# SoftCore_SA_P2_PG5.net
KiCad netlist of a schematic drawn in Altium Designer
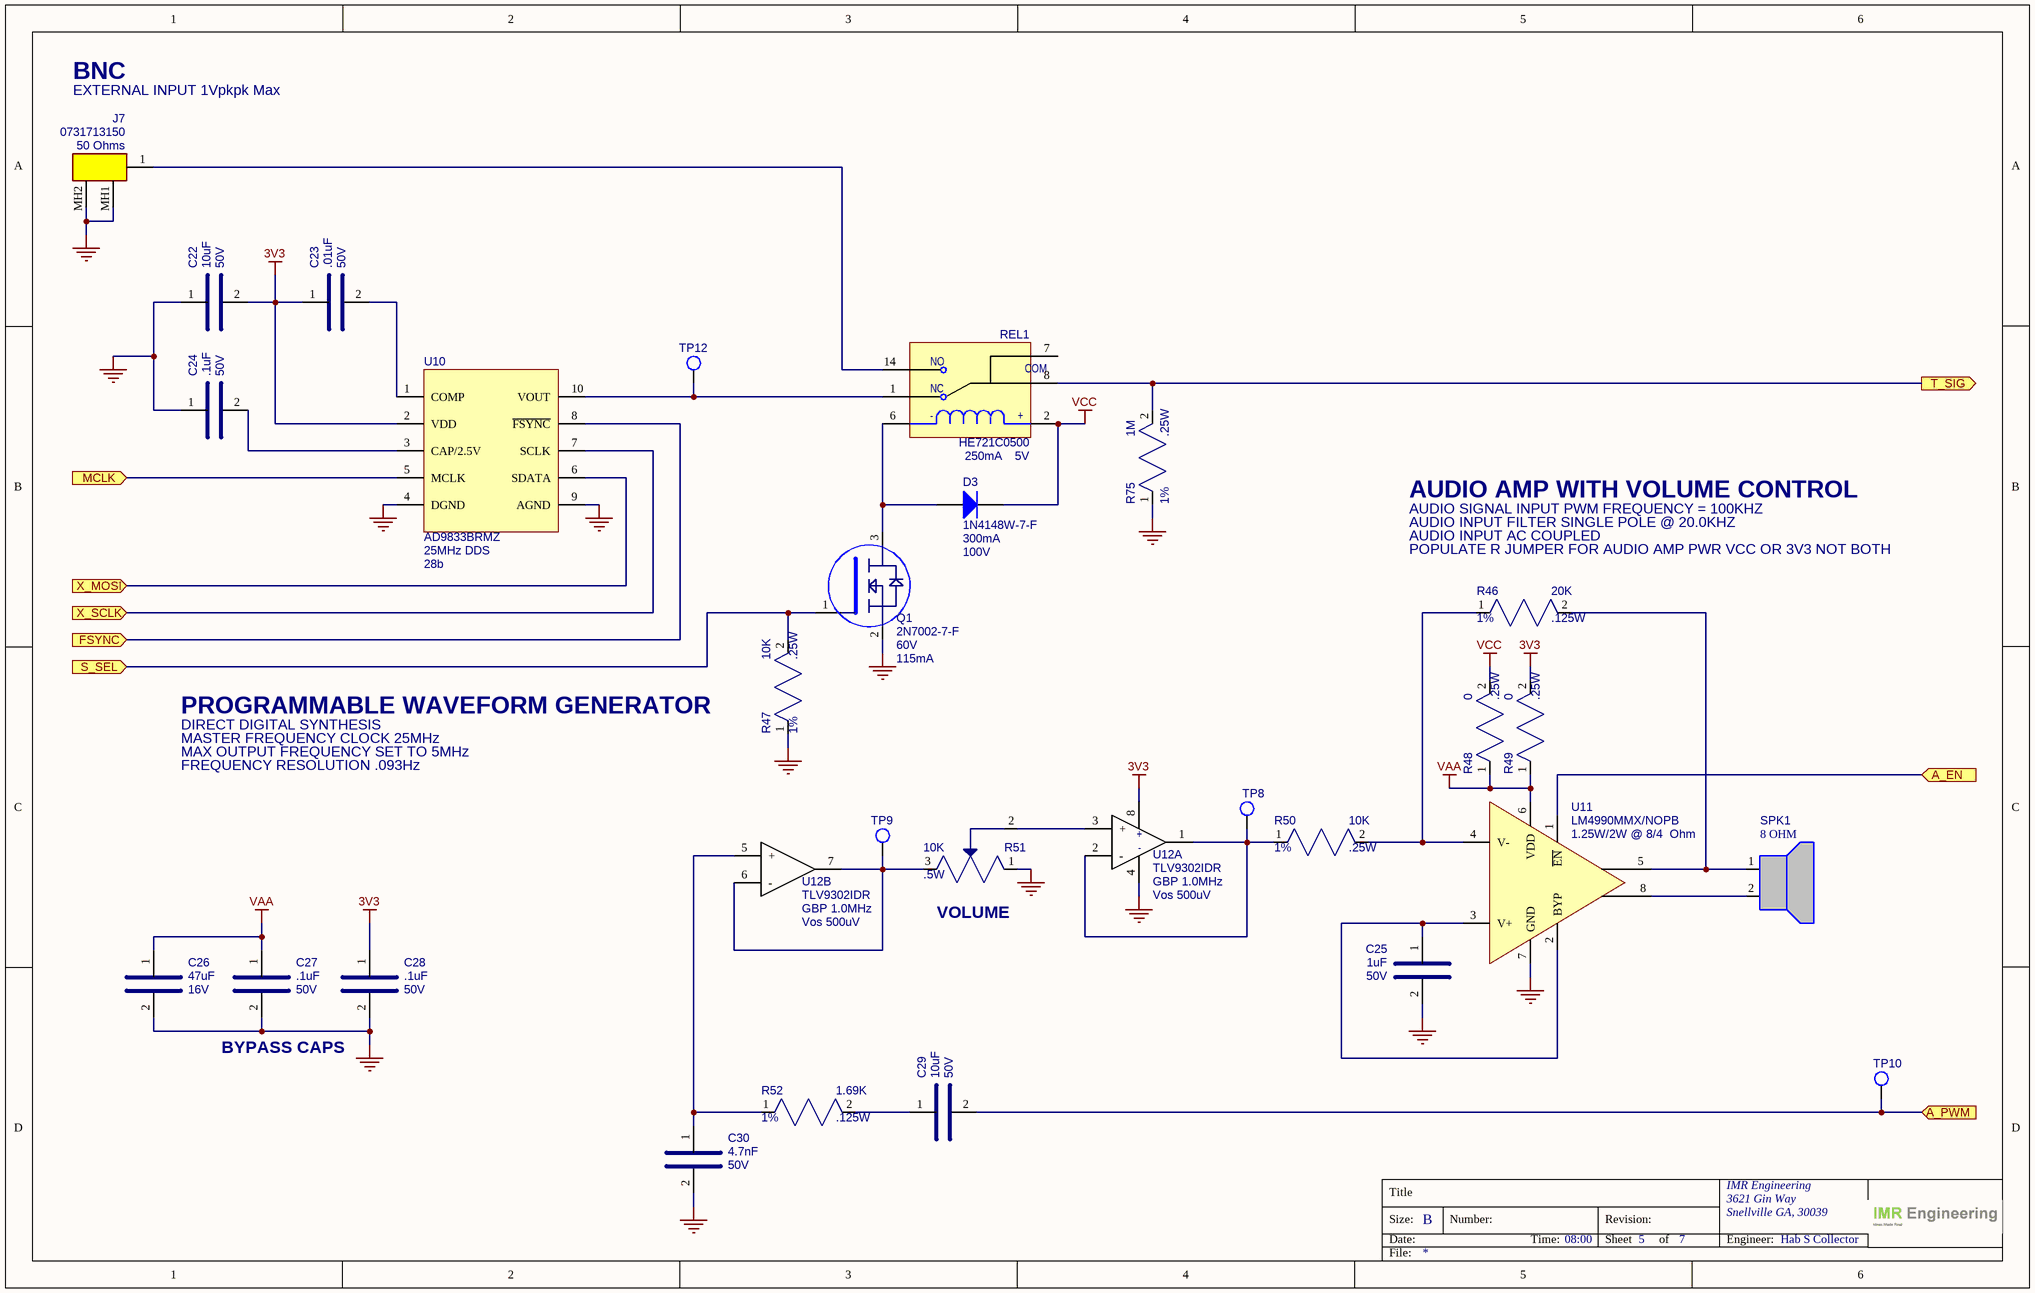
[diagram p0: SoftCore_SA_P2_PG5.SchDoc]

(export (version "E")
  (design (tool "Eeschema 10.0.6"))
  (components
    (comp (ref "C22")
      (value "10uF")
      (footprint "CAP_0805")
      (description "CAP CER 10UF 50V X5R 0805")
      (fields
        (field (name "MFG") "Murata Electronics")
        (field (name "VOLTAGE") "50V")
        (field (name "Comment") "GRM21BR61H106KE43L")
      )
      (libsource (lib "IMR_LIB_SCH_R2") (part "CAP_SMD_10UF_50V_0805"))
    )
    (comp (ref "C23")
      (value ".01uF")
      (footprint "CAP_0805")
      (description "CAP CER 0.01UF 50V X7R 0805")
      (fields
        (field (name "MFG") "KYOCERA AVX")
        (field (name "VOLTAGE") "50V")
        (field (name "Comment") "KGM21NR71H103KT")
      )
      (libsource (lib "IMR_LIB_SCH_R2") (part "CAP_SMD_0.01UF_50V_0805"))
    )
    (comp (ref "C24")
      (value ".1uF")
      (footprint "CAP_0805")
      (description "CAP CER 0.1UF 50V X7R 0805")
      (fields
        (field (name "MFG") "KYOCERA AVX")
        (field (name "VOLTAGE") "50V")
        (field (name "Comment") "KGM21NR71H104KT")
      )
      (libsource (lib "IMR_LIB_SCH_R2") (part "CAP_SMD_0.1UF_50V_0805"))
    )
    (comp (ref "C25")
      (value "1uF")
      (footprint "CAP_0805")
      (description "CAP CER 1UF 50V X7R 0805")
      (fields
        (field (name "MFG") "KYOCERA AVX")
        (field (name "VOLTAGE") "50V")
        (field (name "Comment") "08055C105K4T2A")
      )
      (libsource (lib "IMR_LIB_SCH_R2") (part "CAP_SMD_1UF_50V_0805"))
    )
    (comp (ref "C26")
      (value "47uF")
      (footprint "CAP_1210")
      (description "CAP CER 47UF 50V X5R 1210")
      (fields
        (field (name "MFG") "Murata Electronics")
        (field (name "VOLTAGE") "16V")
        (field (name "Comment") "GRM32ER60J476ME20L")
      )
      (libsource (lib "IMR_LIB_SCH_R2") (part "CAP_SMD_47UF_16V_1210"))
    )
    (comp (ref "C27")
      (value ".1uF")
      (footprint "CAP_0805")
      (description "CAP CER 0.1UF 50V X7R 0805")
      (fields
        (field (name "MFG") "KYOCERA AVX")
        (field (name "VOLTAGE") "50V")
        (field (name "Comment") "KGM21NR71H104KT")
      )
      (libsource (lib "IMR_LIB_SCH_R2") (part "CAP_SMD_0.1UF_50V_0805"))
    )
    (comp (ref "C28")
      (value ".1uF")
      (footprint "CAP_0805")
      (description "CAP CER 0.1UF 50V X7R 0805")
      (fields
        (field (name "MFG") "KYOCERA AVX")
        (field (name "VOLTAGE") "50V")
        (field (name "Comment") "KGM21NR71H104KT")
      )
      (libsource (lib "IMR_LIB_SCH_R2") (part "CAP_SMD_0.1UF_50V_0805"))
    )
    (comp (ref "C29")
      (value "10uF")
      (footprint "CAP_0805")
      (description "CAP CER 10UF 50V X5R 0805")
      (fields
        (field (name "MFG") "Murata Electronics")
        (field (name "VOLTAGE") "50V")
        (field (name "Comment") "GRM21BR61H106KE43L")
      )
      (libsource (lib "IMR_LIB_SCH_R2") (part "CAP_SMD_10UF_50V_0805"))
    )
    (comp (ref "C30")
      (value "4.7nF")
      (footprint "CAP_0805")
      (description "CAP CER 4.7NF 50V X7R 0805")
      (fields
        (field (name "MFG") "KEMET")
        (field (name "VOLTAGE") "50V")
        (field (name "Comment") "C0805C472K5RACAUTO")
      )
      (libsource (lib "IMR_LIB_SCH_R2") (part "CAP_SMD_4.7NF_50V_0805"))
    )
    (comp (ref "D3")
      (value "100V")
      (footprint "SOD123")
      (description "RELAY REED SPDT 250MA 5V")
      (fields
        (field (name "MFG") "Diodes Inc")
        (field (name "MFG_PN") "1N4148W-7-F")
        (field (name "CURRENT") "300mA")
        (field (name "Comment") "1N4148W-7-F")
      )
      (libsource (lib "IMR_LIB_SCH_R2") (part "DIODE_1N4148W-7-F"))
    )
    (comp (ref "J7")
      (value "50 Ohms")
      (footprint "731713150")
      (description "CONN BNC RCPT R/A 50 OHM PCB")
      (fields
        (field (name "MFG") "Molex")
        (field (name "MFG_PN") "0731713150")
        (field (name "Comment") "0731713150")
      )
      (libsource (lib "IMR_LIB_SCH_R2") (part "CONN_MOLEX_0731713150"))
    )
    (comp (ref "Q1")
      (value "60V")
      (footprint "SOT-23")
      (description "MOSFET N-CH 60V 115MA SOT23-3")
      (fields
        (field (name "MFG") "Diodes Inc")
        (field (name "MFG_PN") "2N7002-7-F")
        (field (name "CURRENT") "115mA")
        (field (name "Comment") "2N7002-7-F")
      )
      (libsource (lib "IMR_LIB_SCH_R2") (part "MOSFET_NCH_2N7002-7-F"))
    )
    (comp (ref "R46")
      (value "20K")
      (footprint "RES_0805")
      (description "RES SMD 20K OHM 1% 1/8W 0805")
      (fields
        (field (name "MFG") "Yageo")
        (field (name "POWER") ".125W")
        (field (name "TOLERANCE") "1%")
        (field (name "Comment") "RC0805FR-0720KL")
      )
      (libsource (lib "IMR_LIB_SCH_R2") (part "RES_SMD_20K_0805_1/8W_1%"))
    )
    (comp (ref "R47")
      (value "10K")
      (footprint "RES_0805")
      (description "RES SMD 10K OHM 1% 1/4W 0805")
      (fields
        (field (name "MFG") "Yageo")
        (field (name "POWER") ".25W")
        (field (name "TOLERANCE") "1%")
        (field (name "Comment") "RC0805FR-7W10KL")
      )
      (libsource (lib "IMR_LIB_SCH_R2") (part "RES_SMD_10K_0805_1/4W_1%"))
    )
    (comp (ref "R48")
      (value "0")
      (footprint "RES_0805")
      (description "RES SMD 0 OHM 1% 1/8W 0805")
      (fields (field (name "MFG") "Yageo") (field (name "TOLERANCE") "1%") (field (name "POWER") ".25W"))
      (libsource (lib "IMR_LIB_SCH_R2") (part "RES_SMD_0_0805_1/8W_1%"))
    )
    (comp (ref "R49")
      (value "0")
      (footprint "RES_0805")
      (description "RES SMD 0 OHM 1% 1/8W 0805")
      (fields (field (name "MFG") "Yageo") (field (name "TOLERANCE") "1%") (field (name "POWER") ".25W"))
      (libsource (lib "IMR_LIB_SCH_R2") (part "RES_SMD_0_0805_1/8W_1%"))
    )
    (comp (ref "R50")
      (value "10K")
      (footprint "RES_0805")
      (description "RES SMD 10K OHM 1% 1/4W 0805")
      (fields
        (field (name "MFG") "Yageo")
        (field (name "POWER") ".25W")
        (field (name "TOLERANCE") "1%")
        (field (name "Comment") "RC0805FR-7W10KL")
      )
      (libsource (lib "IMR_LIB_SCH_R2") (part "RES_SMD_10K_0805_1/4W_1%"))
    )
    (comp (ref "R51")
      (value "10K")
      (footprint "BOURNS_3386F")
      (description "POT 10K OHM 1/20W LINEAR - 1X GANG")
      (fields
        (field (name "MFG") "Bourns Inc.")
        (field (name "POWER") ".5W")
        (field (name "Comment") "3386F-1-103TLF")
      )
      (libsource (lib "IMR_LIB_SCH_R2") (part "RES_POT_10K_1XGANG_LINEAR"))
    )
    (comp (ref "R52")
      (value "1.69K")
      (footprint "RES_0805")
      (description "RES SMD 1.69K OHM 1% 1/8W 0805")
      (fields
        (field (name "MFG") "Yageo")
        (field (name "POWER") ".125W")
        (field (name "TOLERANCE") "1%")
        (field (name "Comment") "RC0805FR-071K69L")
      )
      (libsource (lib "IMR_LIB_SCH_R2") (part "RES_SMD_1.69K_0805_1/8W_1%"))
    )
    (comp (ref "R75")
      (value "1M")
      (footprint "RES_0805")
      (description "RES SMD 1M OHM 1% 1/4W 0805")
      (fields
        (field (name "MFG") "Yageo")
        (field (name "POWER") ".25W")
        (field (name "TOLERANCE") "1%")
        (field (name "Comment") "RC0805FR-7W1ML")
      )
      (libsource (lib "IMR_LIB_SCH_R2") (part "RES_SMD_1M_0805_1/4W_1%"))
    )
    (comp (ref "REL1")
      (value "5V")
      (footprint "HE700")
      (description "RELAY REED SPDT 250MA 5V")
      (fields
        (field (name "MFG") "Littlefuse")
        (field (name "MFG_PN") "HE721C0500")
        (field (name "CURRENT") "250mA")
        (field (name "Comment") "HE721C0500")
      )
      (libsource (lib "IMR_LIB_SCH_R2") (part "RELAY_HE721C0500"))
    )
    (comp (ref "SPK1")
      (value "8 OHM")
      (footprint "HDR_1X2_100MILL")
      (description "CONN SPEAKER HEADER GENERIC VERT 2POS 2.54MM")
      (fields (field (name "MFG") "GENERIC") (field (name "Comment") "TBD"))
      (libsource (lib "IMR_LIB_SCH_R2") (part "CONN_SPKR_HEADER_2P_100MIL"))
    )
    (comp (ref "TP8")
      (value "~")
      (footprint "TEST_POINT_35MIL_TH")
      (description "TEST POINT TH FITS DSO PROBE TIP")
      (libsource (lib "IMR_LIB_SCH_R2") (part "CONN_TEST_POINT_TH_PROBE_TIP"))
    )
    (comp (ref "TP9")
      (value "~")
      (footprint "TEST_POINT_35MIL_TH")
      (description "TEST POINT TH FITS DSO PROBE TIP")
      (libsource (lib "IMR_LIB_SCH_R2") (part "CONN_TEST_POINT_TH_PROBE_TIP"))
    )
    (comp (ref "TP10")
      (value "~")
      (footprint "TEST_POINT_35MIL_TH")
      (description "TEST POINT TH FITS DSO PROBE TIP")
      (libsource (lib "IMR_LIB_SCH_R2") (part "CONN_TEST_POINT_TH_PROBE_TIP"))
    )
    (comp (ref "TP12")
      (value "~")
      (footprint "TEST_POINT_35MIL_TH")
      (description "TEST POINT TH FITS DSO PROBE TIP")
      (libsource (lib "IMR_LIB_SCH_R2") (part "CONN_TEST_POINT_TH_PROBE_TIP"))
    )
    (comp (ref "U10")
      (value "25MHz DDS")
      (footprint "RM_10_ADI")
      (description "IC DDS 25MHZ 10BIT 10MSOP")
      (fields
        (field (name "MFG") "Analog Devices")
        (field (name "MFG_PN") "AD9833BRMZ")
        (field (name "TUNING WORD WIDTH") "28b")
        (field (name "Comment") "AD9833BRMZ")
      )
      (libsource (lib "IMR_LIB_SCH_R2") (part "IC_AD9833BRMZ"))
    )
    (comp (ref "U11")
      (value "1.25W/2W @ 8/4  Ohm")
      (footprint "SOP65P490X110-8N")
      (description "IC AMP CLASS AB MONO 2W 8VSSOP")
      (fields
        (field (name "MFG") "Texas Instruments")
        (field (name "MFG_PN") "LM4990MMX/NOPB")
        (field (name "Comment") "LM4990MMX/NOPB")
      )
      (libsource (lib "IMR_LIB_SCH_R2") (part "IC_LM4990MMX/NOPB"))
    )
    (comp (ref "U12")
      (value "GBP 1.0MHz")
      (footprint "SOIC-8_49")
      (description "IC OPAMP GP 2 CIRCUIT 8SOIC")
      (fields
        (field (name "MFG") "Texas Instruments")
        (field (name "MFG_PN") "TLV9302IDR")
        (field (name "VOS") "Vos 500uV")
        (field (name "Comment") "TLV9302IDR")
      )
      (libsource (lib "IMR_LIB_SCH_R2") (part "IC_OPAMP_TLV9302IDR"))
    )
  )
  (nets
    (net (code "1") (name "/A_EN") (class "Default")
      (node (ref "U11") (pin "1") (pinfunction "EN_1") (pintype "passive"))
    )
    (net (code "2") (name "/A_PWM") (class "Default")
      (node (ref "C29") (pin "2") (pinfunction "2_2") (pintype "passive"))
      (node (ref "TP10") (pin "1") (pintype "passive"))
    )
    (net (code "3") (name "/FSYNC") (class "Default")
      (node (ref "U10") (pin "8") (pinfunction "~{FSYNC}_8") (pintype "passive"))
    )
    (net (code "4") (name "/MCLK") (class "Default")
      (node (ref "U10") (pin "5") (pinfunction "MCLK_5") (pintype "passive"))
    )
    (net (code "5") (name "/S_SEL") (class "Default")
      (node (ref "Q1") (pin "1") (pinfunction "B_1") (pintype "passive"))
      (node (ref "R47") (pin "2") (pinfunction "2_2") (pintype "passive"))
    )
    (net (code "6") (name "/T_SIG") (class "Default")
      (node (ref "R75") (pin "2") (pinfunction "2_2") (pintype "passive"))
      (node (ref "REL1") (pin "8") (pinfunction "COM_8") (pintype "passive"))
    )
    (net (code "7") (name "/X_MOSI") (class "Default")
      (node (ref "U10") (pin "6") (pinfunction "SDATA_6") (pintype "passive"))
    )
    (net (code "8") (name "/X_SCLK") (class "Default")
      (node (ref "U10") (pin "7") (pinfunction "SCLK_7") (pintype "passive"))
    )
    (net (code "9") (name "3V3") (class "Default")
      (node (ref "C22") (pin "2") (pinfunction "2_2") (pintype "passive"))
      (node (ref "C23") (pin "1") (pinfunction "1_1") (pintype "passive"))
      (node (ref "C28") (pin "1") (pinfunction "1_1") (pintype "passive"))
      (node (ref "R49") (pin "2") (pinfunction "2_2") (pintype "passive"))
      (node (ref "U10") (pin "2") (pinfunction "VDD_2") (pintype "passive"))
      (node (ref "U12") (pin "8") (pintype "passive"))
    )
    (net (code "10") (name "GND") (class "Default")
      (node (ref "C22") (pin "1") (pinfunction "1_1") (pintype "passive"))
      (node (ref "C24") (pin "1") (pinfunction "1_1") (pintype "passive"))
      (node (ref "C25") (pin "2") (pinfunction "2_2") (pintype "passive"))
      (node (ref "C26") (pin "2") (pinfunction "2_2") (pintype "passive"))
      (node (ref "C27") (pin "2") (pinfunction "2_2") (pintype "passive"))
      (node (ref "C28") (pin "2") (pinfunction "2_2") (pintype "passive"))
      (node (ref "C30") (pin "2") (pinfunction "2_2") (pintype "passive"))
      (node (ref "J7") (pin "MH1") (pintype "passive"))
      (node (ref "J7") (pin "MH2") (pintype "passive"))
      (node (ref "Q1") (pin "2") (pinfunction "E_2") (pintype "passive"))
      (node (ref "R47") (pin "1") (pinfunction "1_1") (pintype "passive"))
      (node (ref "R51") (pin "1") (pinfunction "1_1") (pintype "passive"))
      (node (ref "R75") (pin "1") (pinfunction "1_1") (pintype "passive"))
      (node (ref "U10") (pin "4") (pinfunction "DGND_4") (pintype "passive"))
      (node (ref "U10") (pin "9") (pinfunction "AGND_9") (pintype "passive"))
      (node (ref "U11") (pin "7") (pinfunction "GND_7") (pintype "passive"))
      (node (ref "U12") (pin "4") (pintype "passive"))
    )
    (net (code "11") (name "Net-(C29-Pad1)") (class "Default")
      (node (ref "C29") (pin "1") (pinfunction "1_1") (pintype "passive"))
      (node (ref "R52") (pin "2") (pinfunction "2_2") (pintype "passive"))
    )
    (net (code "12") (name "Net-(D3-A)") (class "Default")
      (node (ref "D3") (pin "1") (pinfunction "A_1") (pintype "passive"))
      (node (ref "Q1") (pin "3") (pinfunction "C_3") (pintype "passive"))
      (node (ref "REL1") (pin "6") (pintype "passive"))
    )
    (net (code "13") (name "Net-(REL1-NC)") (class "Default")
      (node (ref "REL1") (pin "1") (pinfunction "NC_1") (pintype "passive"))
      (node (ref "TP12") (pin "1") (pintype "passive"))
      (node (ref "U10") (pin "10") (pinfunction "VOUT_10") (pintype "passive"))
    )
    (net (code "14") (name "Net-(REL1-NO)") (class "Default")
      (node (ref "J7") (pin "1") (pintype "passive"))
      (node (ref "REL1") (pin "14") (pinfunction "NO_14") (pintype "passive"))
    )
    (net (code "15") (name "Net-(U10-CAP{slash}2.5V)") (class "Default")
      (node (ref "C24") (pin "2") (pinfunction "2_2") (pintype "passive"))
      (node (ref "U10") (pin "3") (pinfunction "CAP/2.5V_3") (pintype "passive"))
    )
    (net (code "16") (name "Net-(U10-COMP)") (class "Default")
      (node (ref "C23") (pin "2") (pinfunction "2_2") (pintype "passive"))
      (node (ref "U10") (pin "1") (pinfunction "COMP_1") (pintype "passive"))
    )
    (net (code "17") (name "Net-(U11-BYP)") (class "Default")
      (node (ref "C25") (pin "1") (pinfunction "1_1") (pintype "passive"))
      (node (ref "U11") (pin "2") (pinfunction "BYP_2") (pintype "passive"))
      (node (ref "U11") (pin "3") (pinfunction "V+_3") (pintype "passive"))
    )
    (net (code "18") (name "Net-(U11-V-)") (class "Default")
      (node (ref "R46") (pin "1") (pinfunction "1_1") (pintype "passive"))
      (node (ref "R50") (pin "2") (pinfunction "2_2") (pintype "passive"))
      (node (ref "U11") (pin "4") (pinfunction "V-_4") (pintype "passive"))
    )
    (net (code "19") (name "Net-(U11-VO1)") (class "Default")
      (node (ref "R46") (pin "2") (pinfunction "2_2") (pintype "passive"))
      (node (ref "SPK1") (pin "1") (pintype "passive"))
      (node (ref "U11") (pin "5") (pinfunction "VO1_5") (pintype "passive"))
    )
    (net (code "20") (name "Net-(U11-VO2)") (class "Default")
      (node (ref "SPK1") (pin "2") (pintype "passive"))
      (node (ref "U11") (pin "8") (pinfunction "VO2_8") (pintype "passive"))
    )
    (net (code "21") (name "Net-(U12A-+)") (class "Default")
      (node (ref "R51") (pin "2") (pinfunction "2_2") (pintype "passive"))
      (node (ref "U12") (pin "3") (pinfunction "+_3") (pintype "passive"))
    )
    (net (code "22") (name "Net-(U12A--)") (class "Default")
      (node (ref "R50") (pin "1") (pinfunction "1_1") (pintype "passive"))
      (node (ref "TP8") (pin "1") (pintype "passive"))
      (node (ref "U12") (pin "1") (pintype "passive"))
      (node (ref "U12") (pin "2") (pinfunction "-_2") (pintype "passive"))
    )
    (net (code "23") (name "Net-(U12B-+)") (class "Default")
      (node (ref "C30") (pin "1") (pinfunction "1_1") (pintype "passive"))
      (node (ref "R52") (pin "1") (pinfunction "1_1") (pintype "passive"))
      (node (ref "U12") (pin "5") (pinfunction "+_5") (pintype "passive"))
    )
    (net (code "24") (name "Net-(U12B--)") (class "Default")
      (node (ref "R51") (pin "3") (pinfunction "3_3") (pintype "passive"))
      (node (ref "TP9") (pin "1") (pintype "passive"))
      (node (ref "U12") (pin "6") (pinfunction "-_6") (pintype "passive"))
      (node (ref "U12") (pin "7") (pintype "passive"))
    )
    (net (code "25") (name "VAA") (class "Default")
      (node (ref "C26") (pin "1") (pinfunction "1_1") (pintype "passive"))
      (node (ref "C27") (pin "1") (pinfunction "1_1") (pintype "passive"))
      (node (ref "R48") (pin "1") (pinfunction "1_1") (pintype "passive"))
      (node (ref "R49") (pin "1") (pinfunction "1_1") (pintype "passive"))
      (node (ref "U11") (pin "6") (pinfunction "VDD_6") (pintype "passive"))
    )
    (net (code "26") (name "VCC") (class "Default")
      (node (ref "D3") (pin "2") (pinfunction "K_2") (pintype "passive"))
      (node (ref "R48") (pin "2") (pinfunction "2_2") (pintype "passive"))
      (node (ref "REL1") (pin "2") (pintype "passive"))
    )
    (net (code "27") (name "unconnected-(REL1-COM-Pad7)") (class "Default")
      (node (ref "REL1") (pin "7") (pinfunction "COM_7") (pintype "passive"))
    )
  )
)
